# Motor_Driver.net
KiCad netlist of a schematic drawn in Altium Designer
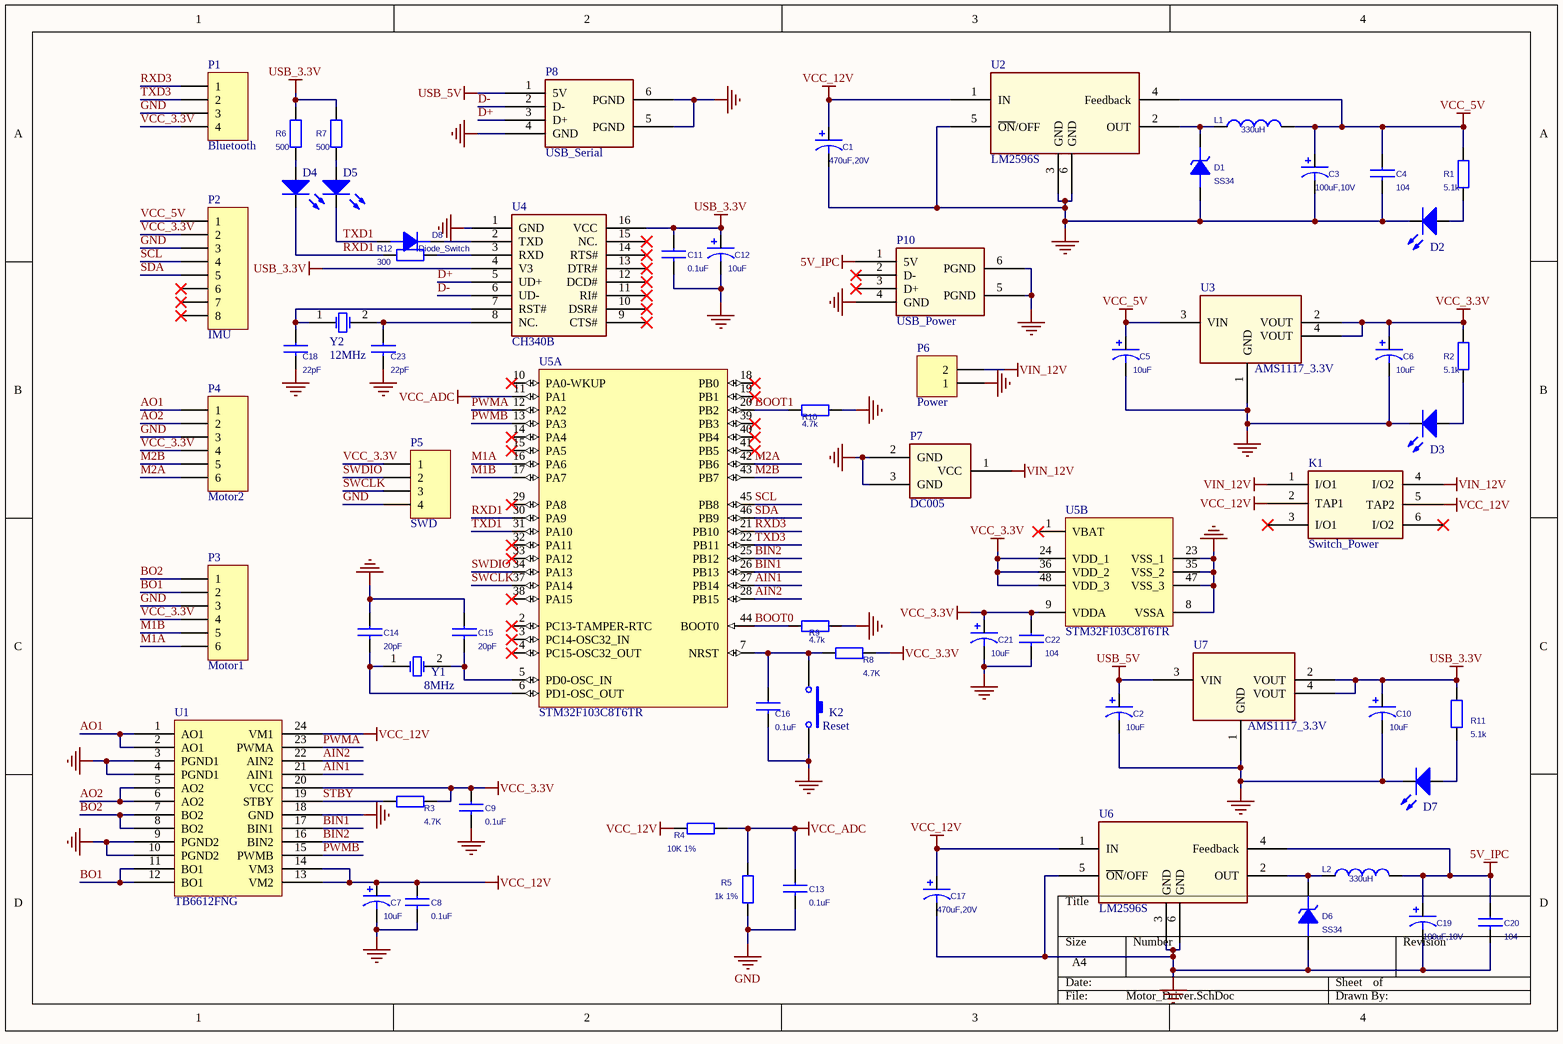
[diagram p0: Motor_Driver.SchDoc]

(export (version "E")
  (design (tool "Eeschema 10.0.6"))
  (components
    (comp (ref "C1")
      (value "470uF,20V")
      (footprint "SMD8102_C")
      (libsource (lib "My_Library") (part "Cap_Polar"))
    )
    (comp (ref "C2")
      (value "10uF")
      (footprint "CAP_CASE_A_3216")
      (libsource (lib "My_Library") (part "Cap_Polar"))
    )
    (comp (ref "C3")
      (value "100uF,10V")
      (footprint "CAP_CASE_C_6032")
      (libsource (lib "My_Library") (part "Cap_Polar"))
    )
    (comp (ref "C4") (value "104") (libsource (lib "My_Library") (part "Cap")))
    (comp (ref "C5")
      (value "10uF")
      (footprint "CAP_CASE_A_3216")
      (libsource (lib "My_Library") (part "Cap_Polar"))
    )
    (comp (ref "C6")
      (value "10uF")
      (footprint "CAP_CASE_A_3216")
      (libsource (lib "My_Library") (part "Cap_Polar"))
    )
    (comp (ref "C7") (value "10uF") (footprint "CAP_1.8R2") (libsource (lib "My_Library") (part "Cap_Polar")))
    (comp (ref "C8") (value "0.1uF") (libsource (lib "My_Library") (part "Cap")))
    (comp (ref "C9") (value "0.1uF") (libsource (lib "My_Library") (part "Cap")))
    (comp (ref "C10")
      (value "10uF")
      (footprint "CAP_CASE_A_3216")
      (libsource (lib "My_Library") (part "Cap_Polar"))
    )
    (comp (ref "C11") (value "0.1uF") (libsource (lib "My_Library") (part "Cap")))
    (comp (ref "C12")
      (value "10uF")
      (footprint "CAP_CASE_A_3216")
      (libsource (lib "My_Library") (part "Cap_Polar"))
    )
    (comp (ref "C13") (value "0.1uF") (libsource (lib "My_Library") (part "Cap")))
    (comp (ref "C14") (value "20pF") (libsource (lib "My_Library") (part "Cap")))
    (comp (ref "C15") (value "20pF") (libsource (lib "My_Library") (part "Cap")))
    (comp (ref "C16") (value "0.1uF") (libsource (lib "My_Library") (part "Cap")))
    (comp (ref "C17")
      (value "470uF,20V")
      (footprint "SMD8102_C")
      (libsource (lib "My_Library") (part "Cap_Polar"))
    )
    (comp (ref "C18") (value "22pF") (libsource (lib "My_Library") (part "Cap")))
    (comp (ref "C19")
      (value "100uF,10V")
      (footprint "CAP_CASE_C_6032")
      (libsource (lib "My_Library") (part "Cap_Polar"))
    )
    (comp (ref "C20") (value "104") (libsource (lib "My_Library") (part "Cap")))
    (comp (ref "C21")
      (value "10uF")
      (footprint "CAP_CASE_A_3216")
      (libsource (lib "My_Library") (part "Cap_Polar"))
    )
    (comp (ref "C22") (value "104") (libsource (lib "My_Library") (part "Cap")))
    (comp (ref "C23") (value "22pF") (libsource (lib "My_Library") (part "Cap")))
    (comp (ref "D1") (value "SS34") (footprint "SMA") (libsource (lib "My_Library") (part "Diode_Zener")))
    (comp (ref "D2") (value "LED_0603") (footprint "LED_0805") (libsource (lib "My_Library") (part "LED")))
    (comp (ref "D3") (value "LED_0603") (footprint "LED_0805") (libsource (lib "My_Library") (part "LED")))
    (comp (ref "D4") (value "LED_0603") (footprint "LED_0805") (libsource (lib "My_Library") (part "LED")))
    (comp (ref "D5") (value "LED_0603") (footprint "LED_0805") (libsource (lib "My_Library") (part "LED")))
    (comp (ref "D6") (value "SS34") (footprint "SMA") (libsource (lib "My_Library") (part "Diode_Zener")))
    (comp (ref "D7") (value "LED_0603") (footprint "LED_0805") (libsource (lib "My_Library") (part "LED")))
    (comp (ref "D8")
      (value "Diode_Switch")
      (footprint "1206_L")
      (libsource (lib "My_Library") (part "Diode_Switch"))
    )
    (comp (ref "K1")
      (value "Switch_Power")
      (footprint "Switch_Key6")
      (libsource (lib "My_Library") (part "Switch_Key6"))
    )
    (comp (ref "K2")
      (value "Reset")
      (footprint "SWITCH_KEY2")
      (libsource (lib "My_Library") (part "Switch_Key2"))
    )
    (comp (ref "L1") (value "330uH") (libsource (lib "My_Library") (part "Inductor")))
    (comp (ref "L2") (value "330uH") (libsource (lib "My_Library") (part "Inductor")))
    (comp (ref "P1")
      (value "Bluetooth")
      (footprint "Connect_4")
      (libsource (lib "My_Library") (part "Connect_4"))
    )
    (comp (ref "P2")
      (value "IMU")
      (footprint "HDR1X8")
      (description "Header, 8-Pin")
      (fields (field (name "PUBLISHER") "Altium Limited"))
      (libsource (lib "Miscellaneous Connectors") (part "Header 8"))
    )
    (comp (ref "P3") (value "Motor1") (footprint "PH2.0_P6") (libsource (lib "My_Library") (part "PH2.0_P6")))
    (comp (ref "P4") (value "Motor2") (footprint "PH2.0_P6") (libsource (lib "My_Library") (part "PH2.0_P6")))
    (comp (ref "P5") (value "SWD") (footprint "Connect_4") (libsource (lib "My_Library") (part "Connect_4")))
    (comp (ref "P6")
      (value "Power")
      (footprint "HT3.96_Power")
      (libsource (lib "My_Library") (part "HT3.96_Power"))
    )
    (comp (ref "P7") (value "DC005") (footprint "DC005") (libsource (lib "My_Library") (part "DC005")))
    (comp (ref "P8")
      (value "USB_Serial")
      (footprint "USB_Pin6")
      (libsource (lib "My_Library") (part "USB_Pin6"))
    )
    (comp (ref "P10")
      (value "USB_Power")
      (footprint "USB_Pin6")
      (libsource (lib "My_Library") (part "USB_Pin6"))
    )
    (comp (ref "R1") (value "5.1k") (footprint "0805_R") (libsource (lib "") (part "Res_1")))
    (comp (ref "R2") (value "5.1k") (footprint "0805_R") (libsource (lib "") (part "Res_1")))
    (comp (ref "R3") (value "4.7K") (footprint "0805_R") (libsource (lib "My_Library") (part "Res")))
    (comp (ref "R4") (value "10K 1%") (footprint "0805_R") (libsource (lib "") (part "Res_2")))
    (comp (ref "R5") (value "1k 1%") (footprint "0805_R") (libsource (lib "") (part "Res_1")))
    (comp (ref "R6") (value "500") (footprint "0805_R") (libsource (lib "") (part "Res_1")))
    (comp (ref "R7") (value "500") (footprint "0805_R") (libsource (lib "") (part "Res_1")))
    (comp (ref "R8") (value "4.7K") (footprint "0805_R") (libsource (lib "My_Library") (part "Res")))
    (comp (ref "R9") (value "4.7k") (footprint "0805_R") (libsource (lib "My_Library") (part "Res")))
    (comp (ref "R10") (value "4.7k") (footprint "0805_R") (libsource (lib "My_Library") (part "Res")))
    (comp (ref "R11") (value "5.1k") (footprint "0805_R") (libsource (lib "") (part "Res_1")))
    (comp (ref "R12") (value "300") (footprint "0805_R") (libsource (lib "My_Library") (part "Res")))
    (comp (ref "U1")
      (value "TB6612FNG")
      (footprint "TB6612FNG")
      (libsource (lib "My_Library") (part "TB6612FNG"))
    )
    (comp (ref "U2") (value "LM2596S") (footprint "LM2596S") (libsource (lib "My_Library") (part "LM2596S")))
    (comp (ref "U3")
      (value "AMS1117_3.3V")
      (footprint "LM1117")
      (libsource (lib "My_Library") (part "AMS1117_3.3V"))
    )
    (comp (ref "U4") (value "CH340B") (footprint "CH340B") (libsource (lib "My_Library") (part "CH340B")))
    (comp (ref "U5")
      (value "STM32F103C8T6TR")
      (footprint "STM-LQFP48_N")
      (libsource (lib "STMicroelectronics STM32 F1") (part "STM32F103C8T6TR"))
    )
    (comp (ref "U6") (value "LM2596S") (footprint "LM2596S") (libsource (lib "My_Library") (part "LM2596S")))
    (comp (ref "U7")
      (value "AMS1117_3.3V")
      (footprint "LM1117")
      (libsource (lib "My_Library") (part "AMS1117_3.3V"))
    )
    (comp (ref "Y1") (value "8MHz") (footprint "Xtal_Pin2") (libsource (lib "My_Library") (part "Xtal_Pin2")))
    (comp (ref "Y2")
      (value "12MHz")
      (footprint "Xtal_Pin2")
      (libsource (lib "My_Library") (part "Xtal_Pin2"))
    )
  )
  (nets
    (net (code "1") (name "/AIN1") (class "Default")
      (node (ref "U1") (pin "21") (pinfunction "AIN1_21") (pintype "passive"))
      (node (ref "U5") (pin "27") (pinfunction "PB14_27") (pintype "bidirectional"))
    )
    (net (code "2") (name "/AIN2") (class "Default")
      (node (ref "U1") (pin "22") (pinfunction "AIN2_22") (pintype "passive"))
      (node (ref "U5") (pin "28") (pinfunction "PB15_28") (pintype "bidirectional"))
    )
    (net (code "3") (name "/AO1") (class "Default")
      (node (ref "P4") (pin "1") (pinfunction "1_1") (pintype "passive"))
      (node (ref "U1") (pin "1") (pinfunction "AO1_1") (pintype "passive"))
      (node (ref "U1") (pin "2") (pinfunction "AO1_2") (pintype "passive"))
    )
    (net (code "4") (name "/AO2") (class "Default")
      (node (ref "P4") (pin "2") (pinfunction "2_2") (pintype "passive"))
      (node (ref "U1") (pin "5") (pinfunction "AO2_5") (pintype "passive"))
      (node (ref "U1") (pin "6") (pinfunction "AO2_6") (pintype "passive"))
    )
    (net (code "5") (name "/BIN1") (class "Default")
      (node (ref "U1") (pin "17") (pinfunction "BIN1_17") (pintype "passive"))
      (node (ref "U5") (pin "26") (pinfunction "PB13_26") (pintype "bidirectional"))
    )
    (net (code "6") (name "/BIN2") (class "Default")
      (node (ref "U1") (pin "16") (pinfunction "BIN2_16") (pintype "passive"))
      (node (ref "U5") (pin "25") (pinfunction "PB12_25") (pintype "bidirectional"))
    )
    (net (code "7") (name "/BO1") (class "Default")
      (node (ref "P3") (pin "2") (pinfunction "2_2") (pintype "passive"))
      (node (ref "U1") (pin "11") (pinfunction "BO1_11") (pintype "passive"))
      (node (ref "U1") (pin "12") (pinfunction "BO1_12") (pintype "passive"))
    )
    (net (code "8") (name "/BO2") (class "Default")
      (node (ref "P3") (pin "1") (pinfunction "1_1") (pintype "passive"))
      (node (ref "U1") (pin "7") (pinfunction "BO2_7") (pintype "passive"))
      (node (ref "U1") (pin "8") (pinfunction "BO2_8") (pintype "passive"))
    )
    (net (code "9") (name "/BOOT0") (class "Default")
      (node (ref "R9") (pin "2") (pinfunction "2_2") (pintype "passive"))
      (node (ref "U5") (pin "44") (pinfunction "BOOT0_44") (pintype "input"))
    )
    (net (code "10") (name "/BOOT1") (class "Default")
      (node (ref "R10") (pin "2") (pinfunction "2_2") (pintype "passive"))
      (node (ref "U5") (pin "20") (pinfunction "PB2_20") (pintype "bidirectional"))
    )
    (net (code "11") (name "/D+") (class "Default")
      (node (ref "P8") (pin "3") (pinfunction "D+_3") (pintype "passive"))
      (node (ref "U4") (pin "5") (pinfunction "UD+_5") (pintype "passive"))
    )
    (net (code "12") (name "/D-") (class "Default")
      (node (ref "P8") (pin "2") (pinfunction "D-_2") (pintype "passive"))
      (node (ref "U4") (pin "6") (pinfunction "UD-_6") (pintype "passive"))
    )
    (net (code "13") (name "/M1A") (class "Default")
      (node (ref "P3") (pin "6") (pinfunction "6_6") (pintype "passive"))
      (node (ref "U5") (pin "16") (pinfunction "PA6_16") (pintype "bidirectional"))
    )
    (net (code "14") (name "/M1B") (class "Default")
      (node (ref "P3") (pin "5") (pinfunction "5_5") (pintype "passive"))
      (node (ref "U5") (pin "17") (pinfunction "PA7_17") (pintype "bidirectional"))
    )
    (net (code "15") (name "/M2A") (class "Default")
      (node (ref "P4") (pin "6") (pinfunction "6_6") (pintype "passive"))
      (node (ref "U5") (pin "42") (pinfunction "PB6_42") (pintype "bidirectional"))
    )
    (net (code "16") (name "/M2B") (class "Default")
      (node (ref "P4") (pin "5") (pinfunction "5_5") (pintype "passive"))
      (node (ref "U5") (pin "43") (pinfunction "PB7_43") (pintype "bidirectional"))
    )
    (net (code "17") (name "/PWMA") (class "Default")
      (node (ref "U1") (pin "23") (pinfunction "PWMA_23") (pintype "passive"))
      (node (ref "U5") (pin "12") (pinfunction "PA2_12") (pintype "bidirectional"))
    )
    (net (code "18") (name "/PWMB") (class "Default")
      (node (ref "U1") (pin "15") (pinfunction "PWMB_15") (pintype "passive"))
      (node (ref "U5") (pin "13") (pinfunction "PA3_13") (pintype "bidirectional"))
    )
    (net (code "19") (name "/RXD1") (class "Default")
      (node (ref "D4") (pin "2") (pinfunction "2_2") (pintype "passive"))
      (node (ref "R12") (pin "2") (pinfunction "2_2") (pintype "passive"))
      (node (ref "U5") (pin "30") (pinfunction "PA9_30") (pintype "bidirectional"))
    )
    (net (code "20") (name "/RXD3") (class "Default")
      (node (ref "P1") (pin "1") (pinfunction "1_1") (pintype "passive"))
      (node (ref "U5") (pin "21") (pinfunction "PB10_21") (pintype "bidirectional"))
    )
    (net (code "21") (name "/SCL") (class "Default")
      (node (ref "P2") (pin "4") (pinfunction "4_4") (pintype "passive"))
      (node (ref "U5") (pin "45") (pinfunction "PB8_45") (pintype "bidirectional"))
    )
    (net (code "22") (name "/SDA") (class "Default")
      (node (ref "P2") (pin "5") (pinfunction "5_5") (pintype "passive"))
      (node (ref "U5") (pin "46") (pinfunction "PB9_46") (pintype "bidirectional"))
    )
    (net (code "23") (name "/STBY") (class "Default")
      (node (ref "R3") (pin "2") (pinfunction "2_2") (pintype "passive"))
      (node (ref "U1") (pin "19") (pinfunction "STBY_19") (pintype "passive"))
    )
    (net (code "24") (name "/SWCLK") (class "Default")
      (node (ref "P5") (pin "3") (pinfunction "3_3") (pintype "passive"))
      (node (ref "U5") (pin "37") (pinfunction "PA14_37") (pintype "bidirectional"))
    )
    (net (code "25") (name "/SWDIO") (class "Default")
      (node (ref "P5") (pin "2") (pinfunction "2_2") (pintype "passive"))
      (node (ref "U5") (pin "34") (pinfunction "PA13_34") (pintype "bidirectional"))
    )
    (net (code "26") (name "/TXD1") (class "Default")
      (node (ref "D5") (pin "2") (pinfunction "2_2") (pintype "passive"))
      (node (ref "D8") (pin "2") (pinfunction "A_2") (pintype "passive"))
      (node (ref "U5") (pin "31") (pinfunction "PA10_31") (pintype "bidirectional"))
    )
    (net (code "27") (name "/TXD3") (class "Default")
      (node (ref "P1") (pin "2") (pinfunction "2_2") (pintype "passive"))
      (node (ref "U5") (pin "22") (pinfunction "PB11_22") (pintype "bidirectional"))
    )
    (net (code "28") (name "5V_IPC") (class "Default")
      (node (ref "C19") (pin "1") (pinfunction "1_1") (pintype "passive"))
      (node (ref "C20") (pin "1") (pinfunction "1_1") (pintype "passive"))
      (node (ref "L2") (pin "2") (pinfunction "2_2") (pintype "passive"))
      (node (ref "P10") (pin "1") (pinfunction "5V_1") (pintype "passive"))
      (node (ref "U6") (pin "4") (pinfunction "Feedback_4") (pintype "passive"))
    )
    (net (code "29") (name "GND") (class "Default")
      (node (ref "C1") (pin "2") (pinfunction "2_2") (pintype "passive"))
      (node (ref "C10") (pin "2") (pinfunction "2_2") (pintype "passive"))
      (node (ref "C11") (pin "2") (pinfunction "2_2") (pintype "passive"))
      (node (ref "C12") (pin "2") (pinfunction "2_2") (pintype "passive"))
      (node (ref "C13") (pin "2") (pinfunction "2_2") (pintype "passive"))
      (node (ref "C14") (pin "1") (pinfunction "1_1") (pintype "passive"))
      (node (ref "C15") (pin "1") (pinfunction "1_1") (pintype "passive"))
      (node (ref "C16") (pin "2") (pinfunction "2_2") (pintype "passive"))
      (node (ref "C17") (pin "2") (pinfunction "2_2") (pintype "passive"))
      (node (ref "C18") (pin "2") (pinfunction "2_2") (pintype "passive"))
      (node (ref "C19") (pin "2") (pinfunction "2_2") (pintype "passive"))
      (node (ref "C2") (pin "2") (pinfunction "2_2") (pintype "passive"))
      (node (ref "C20") (pin "2") (pinfunction "2_2") (pintype "passive"))
      (node (ref "C21") (pin "2") (pinfunction "2_2") (pintype "passive"))
      (node (ref "C22") (pin "2") (pinfunction "2_2") (pintype "passive"))
      (node (ref "C23") (pin "2") (pinfunction "2_2") (pintype "passive"))
      (node (ref "C3") (pin "2") (pinfunction "2_2") (pintype "passive"))
      (node (ref "C4") (pin "2") (pinfunction "2_2") (pintype "passive"))
      (node (ref "C5") (pin "2") (pinfunction "2_2") (pintype "passive"))
      (node (ref "C6") (pin "2") (pinfunction "2_2") (pintype "passive"))
      (node (ref "C7") (pin "2") (pinfunction "2_2") (pintype "passive"))
      (node (ref "C8") (pin "2") (pinfunction "2_2") (pintype "passive"))
      (node (ref "C9") (pin "2") (pinfunction "2_2") (pintype "passive"))
      (node (ref "D1") (pin "2") (pinfunction "ANODE_2") (pintype "passive"))
      (node (ref "D2") (pin "2") (pinfunction "2_2") (pintype "passive"))
      (node (ref "D3") (pin "2") (pinfunction "2_2") (pintype "passive"))
      (node (ref "D6") (pin "2") (pinfunction "ANODE_2") (pintype "passive"))
      (node (ref "D7") (pin "2") (pinfunction "2_2") (pintype "passive"))
      (node (ref "K2") (pin "2") (pinfunction "2_2") (pintype "passive"))
      (node (ref "P1") (pin "3") (pinfunction "3_3") (pintype "passive"))
      (node (ref "P10") (pin "4") (pinfunction "GND_4") (pintype "passive"))
      (node (ref "P10") (pin "5") (pinfunction "PGND_5") (pintype "passive"))
      (node (ref "P10") (pin "6") (pinfunction "PGND_6") (pintype "passive"))
      (node (ref "P2") (pin "3") (pinfunction "3_3") (pintype "passive"))
      (node (ref "P3") (pin "3") (pinfunction "3_3") (pintype "passive"))
      (node (ref "P4") (pin "3") (pinfunction "3_3") (pintype "passive"))
      (node (ref "P5") (pin "4") (pinfunction "4_4") (pintype "passive"))
      (node (ref "P6") (pin "1") (pinfunction "1_1") (pintype "passive"))
      (node (ref "P7") (pin "2") (pinfunction "GND_2") (pintype "passive"))
      (node (ref "P7") (pin "3") (pinfunction "GND_3") (pintype "passive"))
      (node (ref "P8") (pin "4") (pinfunction "GND_4") (pintype "passive"))
      (node (ref "P8") (pin "5") (pinfunction "PGND_5") (pintype "passive"))
      (node (ref "P8") (pin "6") (pinfunction "PGND_6") (pintype "passive"))
      (node (ref "R10") (pin "1") (pinfunction "1_1") (pintype "passive"))
      (node (ref "R5") (pin "1") (pinfunction "1_1") (pintype "passive"))
      (node (ref "R9") (pin "1") (pinfunction "1_1") (pintype "passive"))
      (node (ref "U1") (pin "10") (pinfunction "PGND2_10") (pintype "passive"))
      (node (ref "U1") (pin "18") (pinfunction "GND_18") (pintype "passive"))
      (node (ref "U1") (pin "3") (pinfunction "PGND1_3") (pintype "passive"))
      (node (ref "U1") (pin "4") (pinfunction "PGND1_4") (pintype "passive"))
      (node (ref "U1") (pin "9") (pinfunction "PGND2_9") (pintype "passive"))
      (node (ref "U2") (pin "3") (pinfunction "GND_3") (pintype "passive"))
      (node (ref "U2") (pin "5") (pinfunction "~{ON}/OFF_5") (pintype "passive"))
      (node (ref "U2") (pin "6") (pinfunction "GND_6") (pintype "passive"))
      (node (ref "U3") (pin "1") (pinfunction "GND_1") (pintype "passive"))
      (node (ref "U4") (pin "1") (pinfunction "GND_1") (pintype "passive"))
      (node (ref "U5") (pin "23") (pinfunction "VSS_1_23") (pintype "power_in"))
      (node (ref "U5") (pin "35") (pinfunction "VSS_2_35") (pintype "power_in"))
      (node (ref "U5") (pin "47") (pinfunction "VSS_3_47") (pintype "power_in"))
      (node (ref "U5") (pin "8") (pinfunction "VSSA_8") (pintype "power_in"))
      (node (ref "U6") (pin "3") (pinfunction "GND_3") (pintype "passive"))
      (node (ref "U6") (pin "5") (pinfunction "~{ON}/OFF_5") (pintype "passive"))
      (node (ref "U6") (pin "6") (pinfunction "GND_6") (pintype "passive"))
      (node (ref "U7") (pin "1") (pinfunction "GND_1") (pintype "passive"))
    )
    (net (code "30") (name "Net-(D1-CATHODE)") (class "Default")
      (node (ref "D1") (pin "1") (pinfunction "CATHODE_1") (pintype "passive"))
      (node (ref "L1") (pin "1") (pinfunction "1_1") (pintype "passive"))
      (node (ref "U2") (pin "2") (pinfunction "OUT_2") (pintype "passive"))
    )
    (net (code "31") (name "Net-(D2-Pad1)") (class "Default")
      (node (ref "D2") (pin "1") (pinfunction "1_1") (pintype "passive"))
      (node (ref "R1") (pin "1") (pinfunction "1_1") (pintype "passive"))
    )
    (net (code "32") (name "Net-(D3-Pad1)") (class "Default")
      (node (ref "D3") (pin "1") (pinfunction "1_1") (pintype "passive"))
      (node (ref "R2") (pin "1") (pinfunction "1_1") (pintype "passive"))
    )
    (net (code "33") (name "Net-(D4-Pad1)") (class "Default")
      (node (ref "D4") (pin "1") (pinfunction "1_1") (pintype "passive"))
      (node (ref "R6") (pin "1") (pinfunction "1_1") (pintype "passive"))
    )
    (net (code "34") (name "Net-(D5-Pad1)") (class "Default")
      (node (ref "D5") (pin "1") (pinfunction "1_1") (pintype "passive"))
      (node (ref "R7") (pin "1") (pinfunction "1_1") (pintype "passive"))
    )
    (net (code "35") (name "Net-(D6-CATHODE)") (class "Default")
      (node (ref "D6") (pin "1") (pinfunction "CATHODE_1") (pintype "passive"))
      (node (ref "L2") (pin "1") (pinfunction "1_1") (pintype "passive"))
      (node (ref "U6") (pin "2") (pinfunction "OUT_2") (pintype "passive"))
    )
    (net (code "36") (name "Net-(D7-Pad1)") (class "Default")
      (node (ref "D7") (pin "1") (pinfunction "1_1") (pintype "passive"))
      (node (ref "R11") (pin "1") (pinfunction "1_1") (pintype "passive"))
    )
    (net (code "37") (name "Net-(D8-K)") (class "Default")
      (node (ref "D8") (pin "1") (pinfunction "K_1") (pintype "passive"))
      (node (ref "U4") (pin "2") (pinfunction "TXD_2") (pintype "passive"))
    )
    (net (code "38") (name "Net-(U4-RST#)") (class "Default")
      (node (ref "C18") (pin "1") (pinfunction "1_1") (pintype "passive"))
      (node (ref "U4") (pin "7") (pinfunction "RST#_7") (pintype "passive"))
      (node (ref "Y2") (pin "1") (pinfunction "OSC1_1") (pintype "passive"))
    )
    (net (code "39") (name "Net-(U4-RXD)") (class "Default")
      (node (ref "R12") (pin "1") (pinfunction "1_1") (pintype "passive"))
      (node (ref "U4") (pin "3") (pinfunction "RXD_3") (pintype "passive"))
    )
    (net (code "40") (name "Net-(U5A-NRST)") (class "Default")
      (node (ref "C16") (pin "1") (pinfunction "1_1") (pintype "passive"))
      (node (ref "K2") (pin "1") (pinfunction "1_1") (pintype "passive"))
      (node (ref "R8") (pin "2") (pinfunction "2_2") (pintype "passive"))
      (node (ref "U5") (pin "7") (pinfunction "NRST_7") (pintype "bidirectional"))
    )
    (net (code "41") (name "Net-(U5A-PD0-OSC_IN)") (class "Default")
      (node (ref "C15") (pin "2") (pinfunction "2_2") (pintype "passive"))
      (node (ref "U5") (pin "5") (pinfunction "PD0-OSC_IN_5") (pintype "bidirectional"))
      (node (ref "Y1") (pin "2") (pinfunction "OSC2_2") (pintype "passive"))
    )
    (net (code "42") (name "Net-(U5A-PD1-OSC_OUT)") (class "Default")
      (node (ref "C14") (pin "2") (pinfunction "2_2") (pintype "passive"))
      (node (ref "U5") (pin "6") (pinfunction "PD1-OSC_OUT_6") (pintype "bidirectional"))
      (node (ref "Y1") (pin "1") (pinfunction "OSC1_1") (pintype "passive"))
    )
    (net (code "43") (name "Net-(Y2-OSC2)") (class "Default")
      (node (ref "C23") (pin "1") (pinfunction "1_1") (pintype "passive"))
      (node (ref "U4") (pin "8") (pinfunction "NC._8") (pintype "passive"))
      (node (ref "Y2") (pin "2") (pinfunction "OSC2_2") (pintype "passive"))
    )
    (net (code "44") (name "USB_3.3V") (class "Default")
      (node (ref "C10") (pin "1") (pinfunction "1_1") (pintype "passive"))
      (node (ref "C11") (pin "1") (pinfunction "1_1") (pintype "passive"))
      (node (ref "C12") (pin "1") (pinfunction "1_1") (pintype "passive"))
      (node (ref "R11") (pin "2") (pinfunction "2_2") (pintype "passive"))
      (node (ref "R6") (pin "2") (pinfunction "2_2") (pintype "passive"))
      (node (ref "R7") (pin "2") (pinfunction "2_2") (pintype "passive"))
      (node (ref "U4") (pin "16") (pinfunction "VCC_16") (pintype "passive"))
      (node (ref "U4") (pin "4") (pinfunction "V3_4") (pintype "passive"))
      (node (ref "U7") (pin "2") (pinfunction "VOUT_2") (pintype "passive"))
      (node (ref "U7") (pin "4") (pinfunction "VOUT_4") (pintype "passive"))
    )
    (net (code "45") (name "USB_5V") (class "Default")
      (node (ref "C2") (pin "1") (pinfunction "1_1") (pintype "passive"))
      (node (ref "P8") (pin "1") (pinfunction "5V_1") (pintype "passive"))
      (node (ref "U7") (pin "3") (pinfunction "VIN_3") (pintype "passive"))
    )
    (net (code "46") (name "VCC_3.3V") (class "Default")
      (node (ref "C21") (pin "1") (pinfunction "1_1") (pintype "passive"))
      (node (ref "C22") (pin "1") (pinfunction "1_1") (pintype "passive"))
      (node (ref "C6") (pin "1") (pinfunction "1_1") (pintype "passive"))
      (node (ref "C9") (pin "1") (pinfunction "1_1") (pintype "passive"))
      (node (ref "P1") (pin "4") (pinfunction "4_4") (pintype "passive"))
      (node (ref "P2") (pin "2") (pinfunction "2_2") (pintype "passive"))
      (node (ref "P3") (pin "4") (pinfunction "4_4") (pintype "passive"))
      (node (ref "P4") (pin "4") (pinfunction "4_4") (pintype "passive"))
      (node (ref "P5") (pin "1") (pinfunction "1_1") (pintype "passive"))
      (node (ref "R2") (pin "2") (pinfunction "2_2") (pintype "passive"))
      (node (ref "R3") (pin "1") (pinfunction "1_1") (pintype "passive"))
      (node (ref "R8") (pin "1") (pinfunction "1_1") (pintype "passive"))
      (node (ref "U1") (pin "20") (pinfunction "VCC_20") (pintype "passive"))
      (node (ref "U3") (pin "2") (pinfunction "VOUT_2") (pintype "passive"))
      (node (ref "U3") (pin "4") (pinfunction "VOUT_4") (pintype "passive"))
      (node (ref "U5") (pin "24") (pinfunction "VDD_1_24") (pintype "power_in"))
      (node (ref "U5") (pin "36") (pinfunction "VDD_2_36") (pintype "power_in"))
      (node (ref "U5") (pin "48") (pinfunction "VDD_3_48") (pintype "power_in"))
      (node (ref "U5") (pin "9") (pinfunction "VDDA_9") (pintype "power_in"))
    )
    (net (code "47") (name "VCC_5V") (class "Default")
      (node (ref "C3") (pin "1") (pinfunction "1_1") (pintype "passive"))
      (node (ref "C4") (pin "1") (pinfunction "1_1") (pintype "passive"))
      (node (ref "C5") (pin "1") (pinfunction "1_1") (pintype "passive"))
      (node (ref "L1") (pin "2") (pinfunction "2_2") (pintype "passive"))
      (node (ref "P2") (pin "1") (pinfunction "1_1") (pintype "passive"))
      (node (ref "R1") (pin "2") (pinfunction "2_2") (pintype "passive"))
      (node (ref "U2") (pin "4") (pinfunction "Feedback_4") (pintype "passive"))
      (node (ref "U3") (pin "3") (pinfunction "VIN_3") (pintype "passive"))
    )
    (net (code "48") (name "VCC_12V") (class "Default")
      (node (ref "C1") (pin "1") (pinfunction "1_1") (pintype "passive"))
      (node (ref "C17") (pin "1") (pinfunction "1_1") (pintype "passive"))
      (node (ref "C7") (pin "1") (pinfunction "1_1") (pintype "passive"))
      (node (ref "C8") (pin "1") (pinfunction "1_1") (pintype "passive"))
      (node (ref "K1") (pin "2") (pinfunction "TAP1_2") (pintype "passive"))
      (node (ref "K1") (pin "5") (pinfunction "TAP2_5") (pintype "passive"))
      (node (ref "R4") (pin "1") (pinfunction "1_1") (pintype "passive"))
      (node (ref "U1") (pin "13") (pinfunction "VM2_13") (pintype "passive"))
      (node (ref "U1") (pin "14") (pinfunction "VM3_14") (pintype "passive"))
      (node (ref "U1") (pin "24") (pinfunction "VM1_24") (pintype "passive"))
      (node (ref "U2") (pin "1") (pinfunction "IN_1") (pintype "passive"))
      (node (ref "U6") (pin "1") (pinfunction "IN_1") (pintype "passive"))
    )
    (net (code "49") (name "VCC_ADC") (class "Default")
      (node (ref "C13") (pin "1") (pinfunction "1_1") (pintype "passive"))
      (node (ref "R4") (pin "2") (pinfunction "2_2") (pintype "passive"))
      (node (ref "R5") (pin "2") (pinfunction "2_2") (pintype "passive"))
      (node (ref "U5") (pin "11") (pinfunction "PA1_11") (pintype "bidirectional"))
    )
    (net (code "50") (name "VIN_12V") (class "Default")
      (node (ref "K1") (pin "1") (pinfunction "I/O1_1") (pintype "passive"))
      (node (ref "K1") (pin "4") (pinfunction "I/O2_4") (pintype "passive"))
      (node (ref "P6") (pin "2") (pinfunction "2_2") (pintype "passive"))
      (node (ref "P7") (pin "1") (pinfunction "VCC_1") (pintype "passive"))
    )
    (net (code "51") (name "unconnected-(K1-I{slash}O1-Pad3)") (class "Default")
      (node (ref "K1") (pin "3") (pinfunction "I/O1_3") (pintype "passive+no_connect"))
    )
    (net (code "52") (name "unconnected-(K1-I{slash}O2-Pad6)") (class "Default")
      (node (ref "K1") (pin "6") (pinfunction "I/O2_6") (pintype "passive+no_connect"))
    )
    (net (code "53") (name "unconnected-(P2-Pad6)") (class "Default")
      (node (ref "P2") (pin "6") (pinfunction "6_6") (pintype "passive+no_connect"))
    )
    (net (code "54") (name "unconnected-(P2-Pad7)") (class "Default")
      (node (ref "P2") (pin "7") (pinfunction "7_7") (pintype "passive+no_connect"))
    )
    (net (code "55") (name "unconnected-(P2-Pad8)") (class "Default")
      (node (ref "P2") (pin "8") (pinfunction "8_8") (pintype "passive+no_connect"))
    )
    (net (code "56") (name "unconnected-(P10-D+-Pad3)") (class "Default")
      (node (ref "P10") (pin "3") (pinfunction "D+_3") (pintype "passive+no_connect"))
    )
    (net (code "57") (name "unconnected-(P10-D--Pad2)") (class "Default")
      (node (ref "P10") (pin "2") (pinfunction "D-_2") (pintype "passive+no_connect"))
    )
    (net (code "58") (name "unconnected-(U4-CTS#-Pad9)") (class "Default")
      (node (ref "U4") (pin "9") (pinfunction "CTS#_9") (pintype "passive+no_connect"))
    )
    (net (code "59") (name "unconnected-(U4-DCD#-Pad12)") (class "Default")
      (node (ref "U4") (pin "12") (pinfunction "DCD#_12") (pintype "passive+no_connect"))
    )
    (net (code "60") (name "unconnected-(U4-DSR#-Pad10)") (class "Default")
      (node (ref "U4") (pin "10") (pinfunction "DSR#_10") (pintype "passive+no_connect"))
    )
    (net (code "61") (name "unconnected-(U4-DTR#-Pad13)") (class "Default")
      (node (ref "U4") (pin "13") (pinfunction "DTR#_13") (pintype "passive+no_connect"))
    )
    (net (code "62") (name "unconnected-(U4-NC.-Pad15)") (class "Default")
      (node (ref "U4") (pin "15") (pinfunction "NC._15") (pintype "passive+no_connect"))
    )
    (net (code "63") (name "unconnected-(U4-RI#-Pad11)") (class "Default")
      (node (ref "U4") (pin "11") (pinfunction "RI#_11") (pintype "passive+no_connect"))
    )
    (net (code "64") (name "unconnected-(U4-RTS#-Pad14)") (class "Default")
      (node (ref "U4") (pin "14") (pinfunction "RTS#_14") (pintype "passive+no_connect"))
    )
    (net (code "65") (name "unconnected-(U5A-PA0-WKUP-Pad10)") (class "Default")
      (node (ref "U5") (pin "10") (pinfunction "PA0-WKUP_10") (pintype "bidirectional+no_connect"))
    )
    (net (code "66") (name "unconnected-(U5A-PA4-Pad14)") (class "Default")
      (node (ref "U5") (pin "14") (pinfunction "PA4_14") (pintype "bidirectional+no_connect"))
    )
    (net (code "67") (name "unconnected-(U5A-PA5-Pad15)") (class "Default")
      (node (ref "U5") (pin "15") (pinfunction "PA5_15") (pintype "bidirectional+no_connect"))
    )
    (net (code "68") (name "unconnected-(U5A-PA8-Pad29)") (class "Default")
      (node (ref "U5") (pin "29") (pinfunction "PA8_29") (pintype "bidirectional+no_connect"))
    )
    (net (code "69") (name "unconnected-(U5A-PA11-Pad32)") (class "Default")
      (node (ref "U5") (pin "32") (pinfunction "PA11_32") (pintype "bidirectional+no_connect"))
    )
    (net (code "70") (name "unconnected-(U5A-PA12-Pad33)") (class "Default")
      (node (ref "U5") (pin "33") (pinfunction "PA12_33") (pintype "bidirectional+no_connect"))
    )
    (net (code "71") (name "unconnected-(U5A-PA15-Pad38)") (class "Default")
      (node (ref "U5") (pin "38") (pinfunction "PA15_38") (pintype "bidirectional+no_connect"))
    )
    (net (code "72") (name "unconnected-(U5A-PB0-Pad18)") (class "Default")
      (node (ref "U5") (pin "18") (pinfunction "PB0_18") (pintype "bidirectional+no_connect"))
    )
    (net (code "73") (name "unconnected-(U5A-PB1-Pad19)") (class "Default")
      (node (ref "U5") (pin "19") (pinfunction "PB1_19") (pintype "bidirectional+no_connect"))
    )
    (net (code "74") (name "unconnected-(U5A-PB3-Pad39)") (class "Default")
      (node (ref "U5") (pin "39") (pinfunction "PB3_39") (pintype "bidirectional+no_connect"))
    )
    (net (code "75") (name "unconnected-(U5A-PB4-Pad40)") (class "Default")
      (node (ref "U5") (pin "40") (pinfunction "PB4_40") (pintype "bidirectional+no_connect"))
    )
    (net (code "76") (name "unconnected-(U5A-PB5-Pad41)") (class "Default")
      (node (ref "U5") (pin "41") (pinfunction "PB5_41") (pintype "bidirectional+no_connect"))
    )
    (net (code "77") (name "unconnected-(U5A-PC13-TAMPER-RTC-Pad2)") (class "Default")
      (node (ref "U5") (pin "2") (pinfunction "PC13-TAMPER-RTC_2") (pintype "bidirectional+no_connect"))
    )
    (net (code "78") (name "unconnected-(U5A-PC14-OSC32_IN-Pad3)") (class "Default")
      (node (ref "U5") (pin "3") (pinfunction "PC14-OSC32_IN_3") (pintype "bidirectional+no_connect"))
    )
    (net (code "79") (name "unconnected-(U5A-PC15-OSC32_OUT-Pad4)") (class "Default")
      (node (ref "U5") (pin "4") (pinfunction "PC15-OSC32_OUT_4") (pintype "bidirectional+no_connect"))
    )
    (net (code "80") (name "unconnected-(U5B-VBAT-Pad1)") (class "Default")
      (node (ref "U5") (pin "1") (pinfunction "VBAT_1") (pintype "power_in+no_connect"))
    )
  )
)
